# v010_schematics.net
KiCad netlist of a schematic drawn in Altium Designer
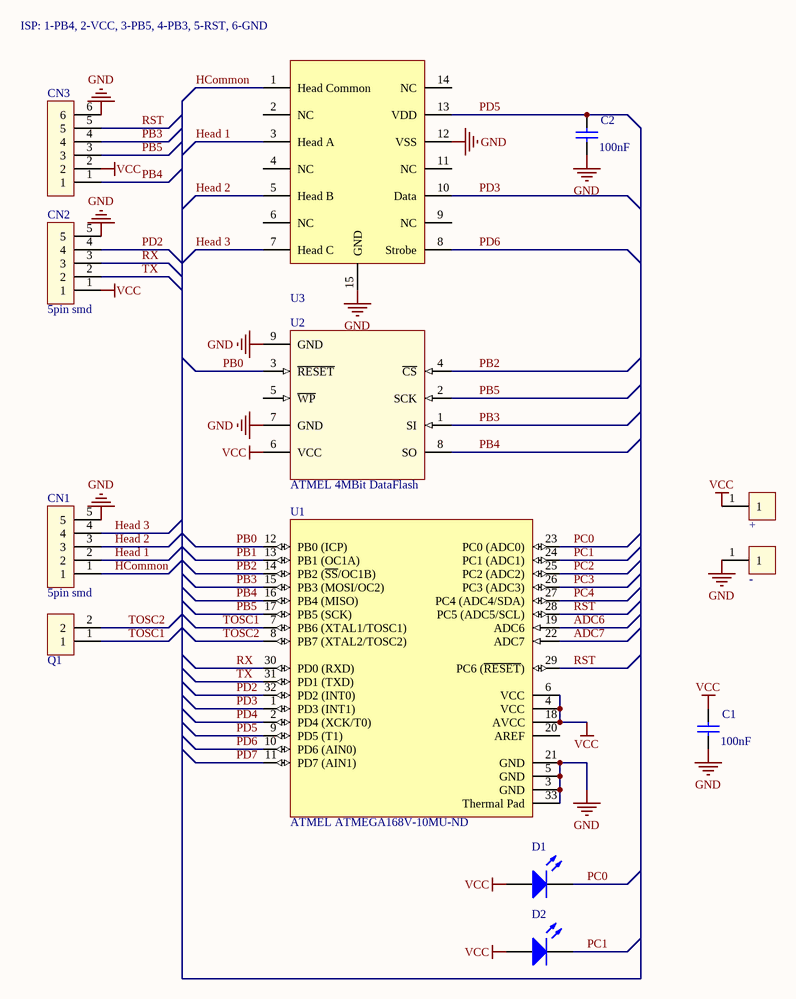
[diagram p0: v010 schematics.SCHDOC]

(export (version "E")
  (design (tool "Eeschema 10.0.6"))
  (components
    (comp (ref "+")
      (value "No component mounted")
      (footprint "SU01LS")
      (libsource (lib "*") (part "1pin smd"))
    )
    (comp (ref "-")
      (value "No component mounted")
      (footprint "SU01LS")
      (libsource (lib "*") (part "1pin smd"))
    )
    (comp (ref "C1")
      (value "100nF")
      (footprint "CC0603(0201)")
      (description "100nf Capacitor - Footprint CC0603 (0201)")
      (fields
        (field (name "DIGI-KEY PART NUMBER") "490-3167-1-ND")
        (field (name "MANUFACTURER") "Murata Electronics")
        (field (name "PUBLISHER") "Altium Limited")
      )
      (libsource (lib "Miscellaneous Devices") (part "Cap"))
    )
    (comp (ref "C2")
      (value "100nF")
      (footprint "CC0603(0201)")
      (description "CAP CER .1UF 6.3V X5R 0201")
      (fields
        (field (name "DIGI-KEY PART NUMBER") "490-3167-1-ND")
        (field (name "PUBLISHER") "Altium Limited")
      )
      (libsource (lib "Miscellaneous Devices") (part "Cap"))
    )
    (comp (ref "CN1")
      (value "5pin smd")
      (footprint "SU05LSR")
      (description "No component mounted")
      (libsource (lib "v4lib") (part "5pin smd"))
    )
    (comp (ref "CN2")
      (value "5pin smd")
      (footprint "SU05LSR")
      (description "No component mounted")
      (libsource (lib "v4lib") (part "5pin smd"))
    )
    (comp (ref "CN3")
      (value "No component mounted")
      (footprint "SU06LST FULL")
      (libsource (lib "v4lib") (part "6pin smd"))
    )
    (comp (ref "D1")
      (value "LED1")
      (footprint "CC1005(0402)")
      (description "LED 0402 GREEN 465NM TRANSPARENT")
      (fields
        (field (name "DIGI-KEY PART NUMBER") "511-1615-1-ND")
        (field (name "MANUFACTURER") "Rohm Semiconductor")
        (field (name "PUBLISHER") "Altium Limited")
      )
      (libsource (lib "Miscellaneous Devices") (part "LED3"))
    )
    (comp (ref "D2")
      (value "LED1")
      (footprint "CC1005(0402)")
      (description "LED 0402 RED 465NM TRANSPARENT")
      (fields
        (field (name "DIGI-KEY PART NUMBER") "511-1615-1-ND")
        (field (name "MANUFACTURER") "Rohm Semiconductor")
        (field (name "PUBLISHER") "Altium Limited")
      )
      (libsource (lib "Miscellaneous Devices") (part "LED3"))
    )
    (comp (ref "Q1")
      (value "32.768khz crystal 1.5 x 3.2mm")
      (footprint "Quartz SMD 2")
      (description "CRYSTAL 32.768KHZ 1.5 x 3.2mm")
      (fields
        (field (name "DIGI-KEY PART NUMBER") "535-9542-1-ND")
        (field (name "MANUFACTURER") "Abracon Corporation")
      )
      (libsource (lib "v4lib") (part "2pin smd"))
    )
    (comp (ref "U1")
      (value "ATMEL ATMEGA168V-10MU-ND")
      (footprint "32M1-A L 5")
      (description "ATMEL ATMEGA168V-10MU")
      (fields
        (field (name "DIGI-KEY PART NUMBER") "ATMEGA168V-10MU-ND")
        (field (name "MANUFACTURER") "ATMEL")
        (field (name "PUBLISHER") "Altium Limited")
      )
      (libsource (lib "Atmel Microcontroller 8-Bit AVR") (part "ATmega8L-8MC"))
    )
    (comp (ref "U2")
      (value "ATMEL 4MBit DataFlash")
      (footprint "8m1-a mlf 4")
      (libsource (lib "v4lib") (part "at45db041b"))
    )
    (comp (ref "U3")
      (value "Asic 3V MLF14")
      (footprint "delta asic - 6")
      (fields (field (name "MANUFACTURER") "Magtek") (field (name "MANUFACTURER PART NUMBER") "21006540"))
      (libsource (lib "v4lib") (part "delta asic 3volt"))
    )
  )
  (nets
    (net (code "1") (name "/ADC6") (class "Default")
      (node (ref "U1") (pin "19") (pinfunction "ADC6_19") (pintype "input"))
    )
    (net (code "2") (name "/ADC7") (class "Default")
      (node (ref "U1") (pin "22") (pinfunction "ADC7_22") (pintype "input"))
    )
    (net (code "3") (name "/HCommon") (class "Default")
      (node (ref "CN1") (pin "1") (pinfunction "1_1") (pintype "passive"))
      (node (ref "U3") (pin "1") (pinfunction "Head_Common_1") (pintype "passive"))
    )
    (net (code "4") (name "/Head 1") (class "Default")
      (node (ref "CN1") (pin "2") (pinfunction "2_2") (pintype "passive"))
      (node (ref "U3") (pin "3") (pinfunction "Head_A_3") (pintype "passive"))
    )
    (net (code "5") (name "/Head 2") (class "Default")
      (node (ref "CN1") (pin "3") (pinfunction "3_3") (pintype "passive"))
      (node (ref "U3") (pin "5") (pinfunction "Head_B_5") (pintype "passive"))
    )
    (net (code "6") (name "/Head 3") (class "Default")
      (node (ref "CN1") (pin "4") (pinfunction "4_4") (pintype "passive"))
      (node (ref "U3") (pin "7") (pinfunction "Head_C_7") (pintype "passive"))
    )
    (net (code "7") (name "/PB0") (class "Default")
      (node (ref "U1") (pin "12") (pinfunction "PB0_(ICP)_12") (pintype "bidirectional"))
      (node (ref "U2") (pin "3") (pinfunction "~{RESET}_3") (pintype "input"))
    )
    (net (code "8") (name "/PB1") (class "Default")
      (node (ref "U1") (pin "13") (pinfunction "PB1_(OC1A)_13") (pintype "bidirectional"))
    )
    (net (code "9") (name "/PB2") (class "Default")
      (node (ref "U1") (pin "14") (pinfunction "PB2_(~{SS}/OC1B)_14") (pintype "bidirectional"))
      (node (ref "U2") (pin "4") (pinfunction "~{CS}_4") (pintype "input"))
    )
    (net (code "10") (name "/PB3") (class "Default")
      (node (ref "CN3") (pin "4") (pinfunction "4_4") (pintype "passive"))
      (node (ref "U1") (pin "15") (pinfunction "PB3_(MOSI/OC2)_15") (pintype "bidirectional"))
      (node (ref "U2") (pin "1") (pinfunction "SI_1") (pintype "input"))
    )
    (net (code "11") (name "/PB4") (class "Default")
      (node (ref "CN3") (pin "1") (pinfunction "1_1") (pintype "passive"))
      (node (ref "U1") (pin "16") (pinfunction "PB4_(MISO)_16") (pintype "bidirectional"))
      (node (ref "U2") (pin "8") (pinfunction "SO_8") (pintype "passive"))
    )
    (net (code "12") (name "/PB5") (class "Default")
      (node (ref "CN3") (pin "3") (pinfunction "3_3") (pintype "passive"))
      (node (ref "U1") (pin "17") (pinfunction "PB5_(SCK)_17") (pintype "bidirectional"))
      (node (ref "U2") (pin "2") (pinfunction "SCK_2") (pintype "input"))
    )
    (net (code "13") (name "/PC0") (class "Default")
      (node (ref "D1") (pin "2") (pinfunction "K_2") (pintype "passive"))
      (node (ref "U1") (pin "23") (pinfunction "PC0_(ADC0)_23") (pintype "bidirectional"))
    )
    (net (code "14") (name "/PC1") (class "Default")
      (node (ref "D2") (pin "2") (pinfunction "K_2") (pintype "passive"))
      (node (ref "U1") (pin "24") (pinfunction "PC1_(ADC1)_24") (pintype "bidirectional"))
    )
    (net (code "15") (name "/PC2") (class "Default")
      (node (ref "U1") (pin "25") (pinfunction "PC2_(ADC2)_25") (pintype "bidirectional"))
    )
    (net (code "16") (name "/PC3") (class "Default")
      (node (ref "U1") (pin "26") (pinfunction "PC3_(ADC3)_26") (pintype "bidirectional"))
    )
    (net (code "17") (name "/PC4") (class "Default")
      (node (ref "U1") (pin "27") (pinfunction "PC4_(ADC4/SDA)_27") (pintype "bidirectional"))
    )
    (net (code "18") (name "/PD2") (class "Default")
      (node (ref "CN2") (pin "4") (pinfunction "4_4") (pintype "passive"))
      (node (ref "U1") (pin "32") (pinfunction "PD2_(INT0)_32") (pintype "bidirectional"))
    )
    (net (code "19") (name "/PD3") (class "Default")
      (node (ref "U1") (pin "1") (pinfunction "PD3_(INT1)_1") (pintype "bidirectional"))
      (node (ref "U3") (pin "10") (pinfunction "Data_10") (pintype "passive"))
    )
    (net (code "20") (name "/PD4") (class "Default")
      (node (ref "U1") (pin "2") (pinfunction "PD4_(XCK/T0)_2") (pintype "bidirectional"))
    )
    (net (code "21") (name "/PD5") (class "Default")
      (node (ref "C2") (pin "1") (pinfunction "1_1") (pintype "passive"))
      (node (ref "U1") (pin "9") (pinfunction "PD5_(T1)_9") (pintype "bidirectional"))
      (node (ref "U3") (pin "13") (pinfunction "VDD_13") (pintype "passive"))
    )
    (net (code "22") (name "/PD6") (class "Default")
      (node (ref "U1") (pin "10") (pinfunction "PD6_(AIN0)_10") (pintype "bidirectional"))
      (node (ref "U3") (pin "8") (pinfunction "Strobe_8") (pintype "passive"))
    )
    (net (code "23") (name "/PD7") (class "Default")
      (node (ref "U1") (pin "11") (pinfunction "PD7_(AIN1)_11") (pintype "bidirectional"))
    )
    (net (code "24") (name "/RST") (class "Default")
      (node (ref "CN3") (pin "5") (pinfunction "5_5") (pintype "passive"))
      (node (ref "U1") (pin "28") (pinfunction "PC5_(ADC5/SCL)_28") (pintype "bidirectional"))
      (node (ref "U1") (pin "29") (pinfunction "PC6_(~{RESET})_29") (pintype "bidirectional"))
    )
    (net (code "25") (name "/RX") (class "Default")
      (node (ref "CN2") (pin "3") (pinfunction "3_3") (pintype "passive"))
      (node (ref "U1") (pin "30") (pinfunction "PD0_(RXD)_30") (pintype "bidirectional"))
    )
    (net (code "26") (name "/TOSC1") (class "Default")
      (node (ref "Q1") (pin "1") (pinfunction "1_1") (pintype "passive"))
      (node (ref "U1") (pin "7") (pinfunction "PB6_(XTAL1/TOSC1)_7") (pintype "bidirectional"))
    )
    (net (code "27") (name "/TOSC2") (class "Default")
      (node (ref "Q1") (pin "2") (pinfunction "2_2") (pintype "passive"))
      (node (ref "U1") (pin "8") (pinfunction "PB7_(XTAL2/TOSC2)_8") (pintype "bidirectional"))
    )
    (net (code "28") (name "/TX") (class "Default")
      (node (ref "CN2") (pin "2") (pinfunction "2_2") (pintype "passive"))
      (node (ref "U1") (pin "31") (pinfunction "PD1_(TXD)_31") (pintype "bidirectional"))
    )
    (net (code "29") (name "GND") (class "Default")
      (node (ref "-") (pin "1") (pinfunction "1_1") (pintype "passive"))
      (node (ref "C1") (pin "2") (pinfunction "2_2") (pintype "passive"))
      (node (ref "C2") (pin "2") (pinfunction "2_2") (pintype "passive"))
      (node (ref "CN1") (pin "5") (pinfunction "5_5") (pintype "passive"))
      (node (ref "CN2") (pin "5") (pinfunction "5_5") (pintype "passive"))
      (node (ref "CN3") (pin "6") (pinfunction "6_6") (pintype "passive"))
      (node (ref "U1") (pin "21") (pinfunction "GND_21") (pintype "power_in"))
      (node (ref "U1") (pin "3") (pinfunction "GND_3") (pintype "power_in"))
      (node (ref "U1") (pin "33") (pinfunction "Thermal_Pad_33") (pintype "power_in"))
      (node (ref "U1") (pin "5") (pinfunction "GND_5") (pintype "power_in"))
      (node (ref "U2") (pin "7") (pinfunction "GND_7") (pintype "passive"))
      (node (ref "U2") (pin "9") (pinfunction "GND_9") (pintype "passive"))
      (node (ref "U3") (pin "12") (pinfunction "VSS_12") (pintype "passive"))
      (node (ref "U3") (pin "15") (pinfunction "GND_15") (pintype "passive"))
    )
    (net (code "30") (name "VCC") (class "Default")
      (node (ref "+") (pin "1") (pinfunction "1_1") (pintype "passive"))
      (node (ref "C1") (pin "1") (pinfunction "1_1") (pintype "passive"))
      (node (ref "CN2") (pin "1") (pinfunction "1_1") (pintype "passive"))
      (node (ref "CN3") (pin "2") (pinfunction "2_2") (pintype "passive"))
      (node (ref "D1") (pin "1") (pinfunction "A_1") (pintype "passive"))
      (node (ref "D2") (pin "1") (pinfunction "A_1") (pintype "passive"))
      (node (ref "U1") (pin "18") (pinfunction "AVCC_18") (pintype "power_in"))
      (node (ref "U1") (pin "4") (pinfunction "VCC_4") (pintype "power_in"))
      (node (ref "U1") (pin "6") (pinfunction "VCC_6") (pintype "power_in"))
      (node (ref "U2") (pin "6") (pinfunction "VCC_6") (pintype "power_in"))
    )
    (net (code "31") (name "unconnected-(U1-AREF-Pad20)") (class "Default")
      (node (ref "U1") (pin "20") (pinfunction "AREF_20") (pintype "passive"))
    )
    (net (code "32") (name "unconnected-(U2-~{WP}-Pad5)") (class "Default")
      (node (ref "U2") (pin "5") (pinfunction "~{WP}_5") (pintype "input"))
    )
    (net (code "33") (name "unconnected-(U3-NC-Pad2)") (class "Default")
      (node (ref "U3") (pin "2") (pinfunction "NC_2") (pintype "passive"))
    )
    (net (code "34") (name "unconnected-(U3-NC-Pad4)") (class "Default")
      (node (ref "U3") (pin "4") (pinfunction "NC_4") (pintype "passive"))
    )
    (net (code "35") (name "unconnected-(U3-NC-Pad6)") (class "Default")
      (node (ref "U3") (pin "6") (pinfunction "NC_6") (pintype "passive"))
    )
    (net (code "36") (name "unconnected-(U3-NC-Pad9)") (class "Default")
      (node (ref "U3") (pin "9") (pinfunction "NC_9") (pintype "passive"))
    )
    (net (code "37") (name "unconnected-(U3-NC-Pad11)") (class "Default")
      (node (ref "U3") (pin "11") (pinfunction "NC_11") (pintype "passive"))
    )
    (net (code "38") (name "unconnected-(U3-NC-Pad14)") (class "Default")
      (node (ref "U3") (pin "14") (pinfunction "NC_14") (pintype "passive"))
    )
  )
)
